# Headstage_Mainboard.net
KiCad netlist of a schematic drawn in Altium Designer
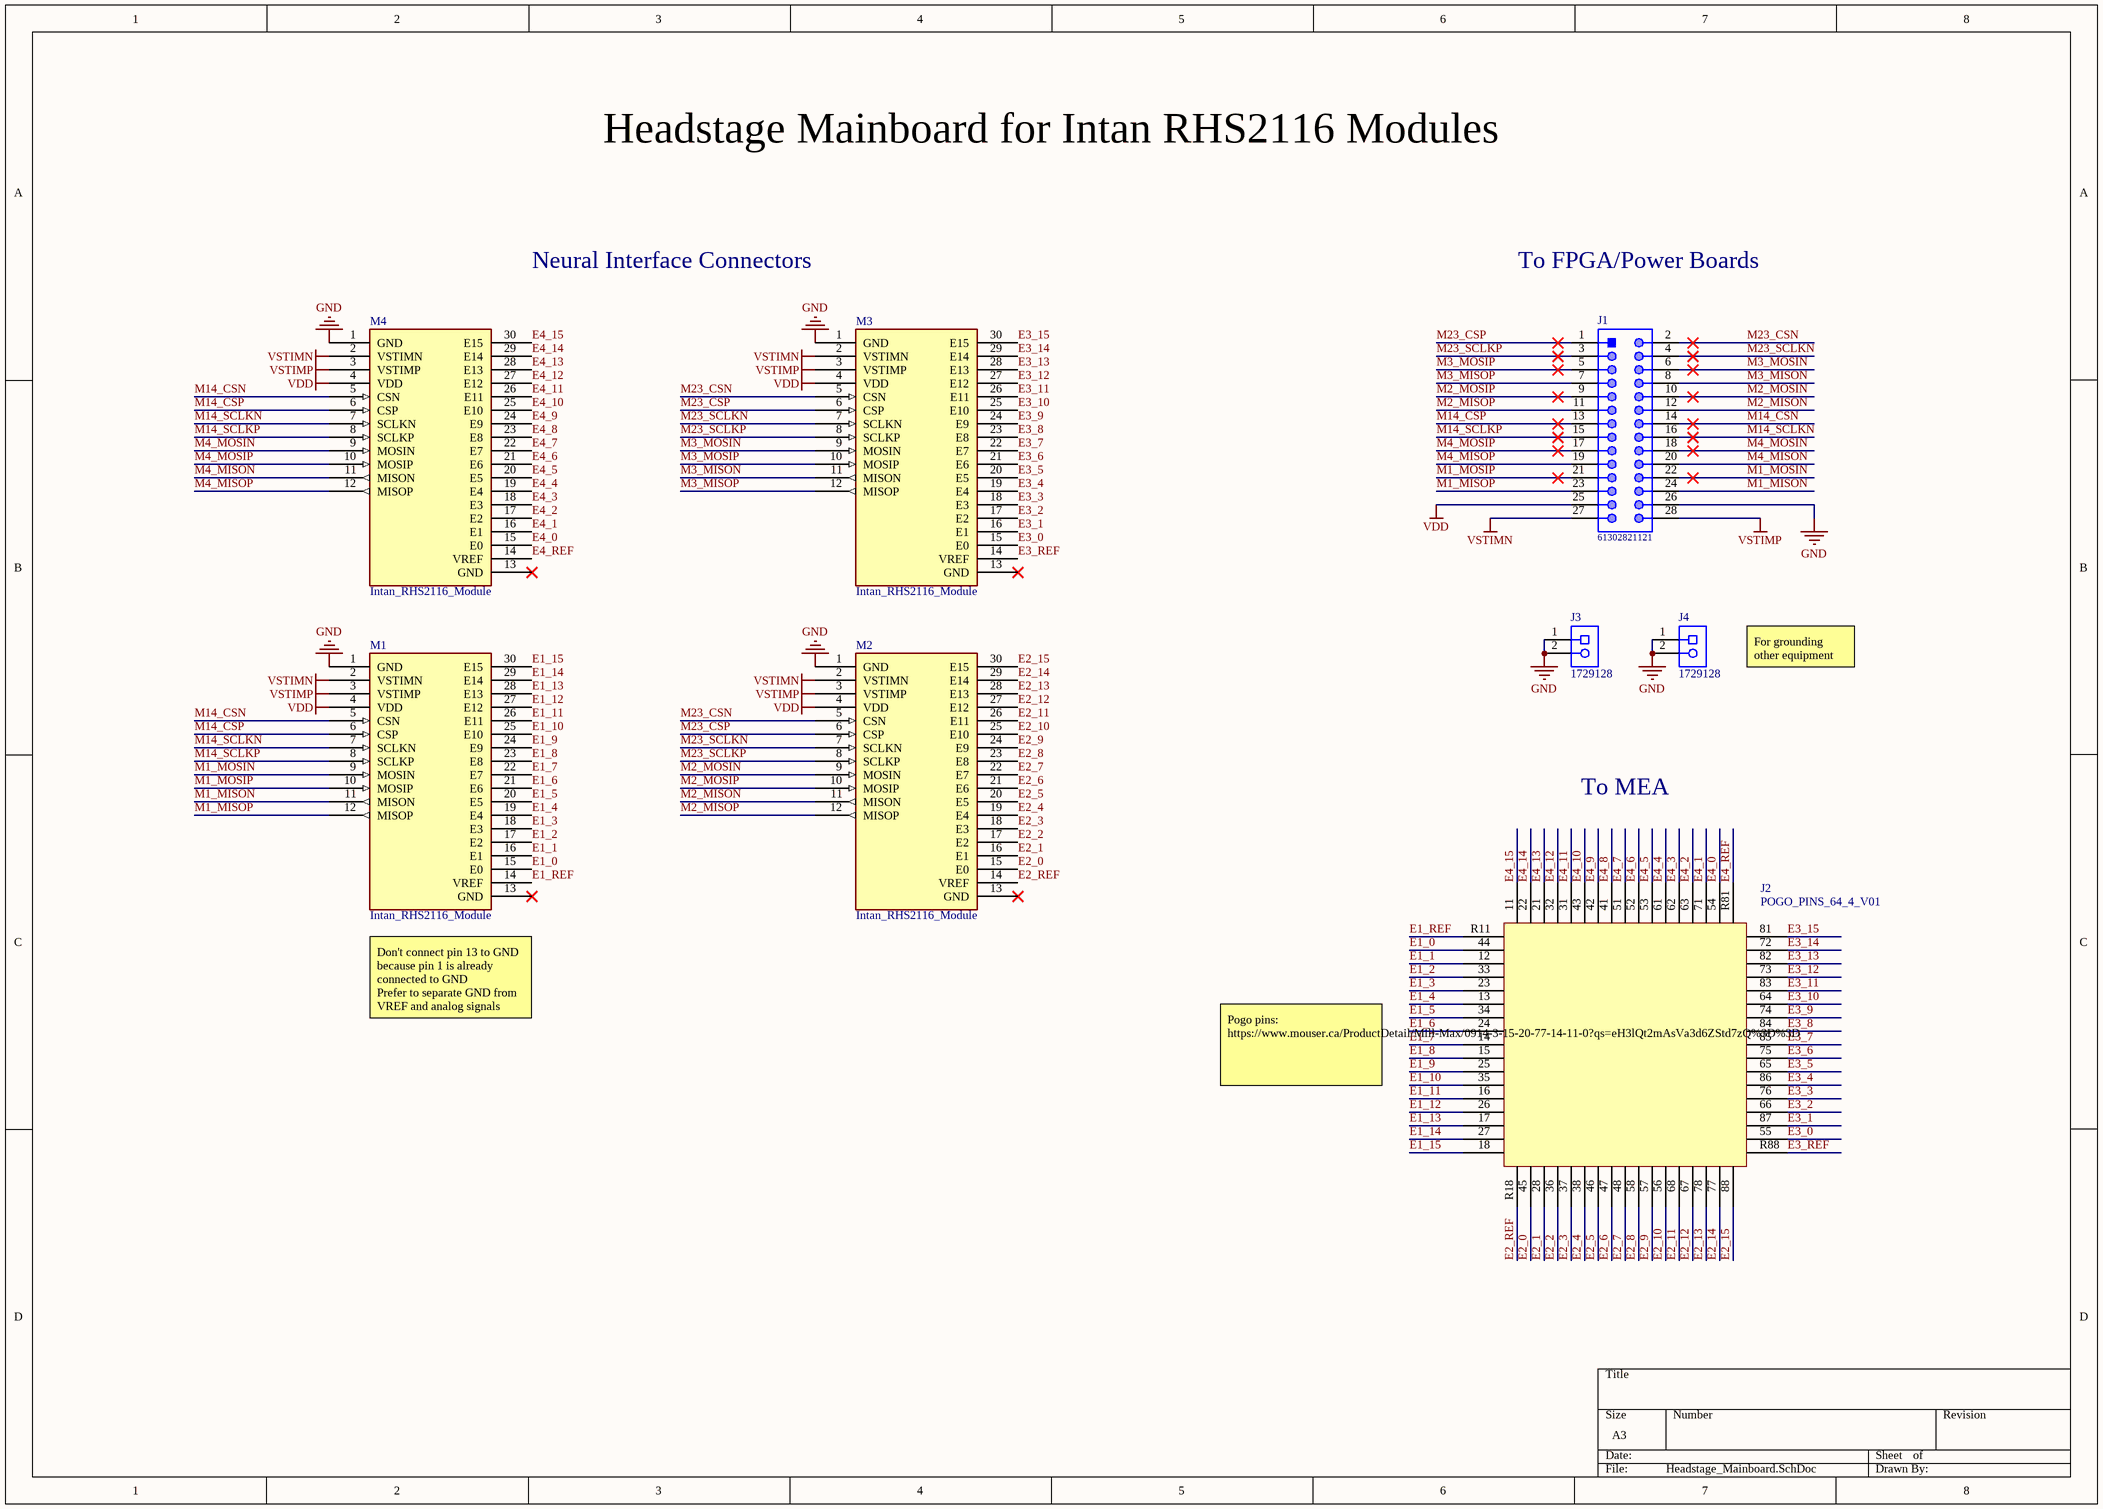
[diagram p0: Headstage_Mainboard.SchDoc]

(export (version "E")
  (design (tool "Eeschema 10.0.6"))
  (components
    (comp (ref "J1")
      (value "61302821121")
      (footprint "61302821121")
      (description "THT Vertical Pin Header WR-PHD, Pitch 2.54 mm, Dual Row, 28 pins")
      (fields (field (name "MANUFACTURER") "Wurth Elektronik") (field (name "PUBLISHER") "WurthElektronik"))
      (libsource (lib "Altium Content Vault") (part "WE-CN-2P-M-R28"))
    )
    (comp (ref "J2")
      (value "POGO_PINS_64_4_V01")
      (footprint "POGO_PINS_64_4_V01")
      (description "Pogo pins, 64 recording, 4 reference, v01")
      (libsource (lib "OpenMEA") (part "POGO_PINS_64_4_V01"))
    )
    (comp (ref "J3")
      (value "1729128")
      (footprint "PHOE-1729128-2_V")
      (description "PCB Terminal Block, 13.5 A, 400 V, 2-Pin THD, RoHS, Bulk")
      (fields (field (name "MANUFACTURER") "Phoenix Contact"))
      (libsource (lib "Altium Content Vault") (part "CN-2P-F-R2"))
    )
    (comp (ref "J4")
      (value "1729128")
      (footprint "PHOE-1729128-2_V")
      (description "PCB Terminal Block, 13.5 A, 400 V, 2-Pin THD, RoHS, Bulk")
      (fields (field (name "MANUFACTURER") "Phoenix Contact"))
      (libsource (lib "Altium Content Vault") (part "CN-2P-F-R2"))
    )
    (comp (ref "M1")
      (value "Intan_RHS2116_Module")
      (footprint "Intan_RHS2116_Module")
      (libsource (lib "OpenMEA") (part "Intan_RHS2116_Module"))
    )
    (comp (ref "M2")
      (value "Intan_RHS2116_Module")
      (footprint "Intan_RHS2116_Module")
      (libsource (lib "OpenMEA") (part "Intan_RHS2116_Module"))
    )
    (comp (ref "M3")
      (value "Intan_RHS2116_Module")
      (footprint "Intan_RHS2116_Module")
      (libsource (lib "OpenMEA") (part "Intan_RHS2116_Module"))
    )
    (comp (ref "M4")
      (value "Intan_RHS2116_Module")
      (footprint "Intan_RHS2116_Module")
      (libsource (lib "OpenMEA") (part "Intan_RHS2116_Module"))
    )
  )
  (nets
    (net (code "1") (name "/E1_0") (class "Default")
      (node (ref "J2") (pin "44") (pintype "passive"))
      (node (ref "M1") (pin "15") (pinfunction "E0_15") (pintype "passive"))
    )
    (net (code "2") (name "/E1_1") (class "Default")
      (node (ref "J2") (pin "12") (pintype "passive"))
      (node (ref "M1") (pin "16") (pinfunction "E1_16") (pintype "passive"))
    )
    (net (code "3") (name "/E1_2") (class "Default")
      (node (ref "J2") (pin "33") (pintype "passive"))
      (node (ref "M1") (pin "17") (pinfunction "E2_17") (pintype "passive"))
    )
    (net (code "4") (name "/E1_3") (class "Default")
      (node (ref "J2") (pin "23") (pintype "passive"))
      (node (ref "M1") (pin "18") (pinfunction "E3_18") (pintype "passive"))
    )
    (net (code "5") (name "/E1_4") (class "Default")
      (node (ref "J2") (pin "13") (pintype "passive"))
      (node (ref "M1") (pin "19") (pinfunction "E4_19") (pintype "passive"))
    )
    (net (code "6") (name "/E1_5") (class "Default")
      (node (ref "J2") (pin "34") (pintype "passive"))
      (node (ref "M1") (pin "20") (pinfunction "E5_20") (pintype "passive"))
    )
    (net (code "7") (name "/E1_6") (class "Default")
      (node (ref "J2") (pin "24") (pintype "passive"))
      (node (ref "M1") (pin "21") (pinfunction "E6_21") (pintype "passive"))
    )
    (net (code "8") (name "/E1_7") (class "Default")
      (node (ref "J2") (pin "14") (pintype "passive"))
      (node (ref "M1") (pin "22") (pinfunction "E7_22") (pintype "passive"))
    )
    (net (code "9") (name "/E1_8") (class "Default")
      (node (ref "J2") (pin "15") (pintype "passive"))
      (node (ref "M1") (pin "23") (pinfunction "E8_23") (pintype "passive"))
    )
    (net (code "10") (name "/E1_9") (class "Default")
      (node (ref "J2") (pin "25") (pintype "passive"))
      (node (ref "M1") (pin "24") (pinfunction "E9_24") (pintype "passive"))
    )
    (net (code "11") (name "/E1_10") (class "Default")
      (node (ref "J2") (pin "35") (pintype "passive"))
      (node (ref "M1") (pin "25") (pinfunction "E10_25") (pintype "passive"))
    )
    (net (code "12") (name "/E1_11") (class "Default")
      (node (ref "J2") (pin "16") (pintype "passive"))
      (node (ref "M1") (pin "26") (pinfunction "E11_26") (pintype "passive"))
    )
    (net (code "13") (name "/E1_12") (class "Default")
      (node (ref "J2") (pin "26") (pintype "passive"))
      (node (ref "M1") (pin "27") (pinfunction "E12_27") (pintype "passive"))
    )
    (net (code "14") (name "/E1_13") (class "Default")
      (node (ref "J2") (pin "17") (pintype "passive"))
      (node (ref "M1") (pin "28") (pinfunction "E13_28") (pintype "passive"))
    )
    (net (code "15") (name "/E1_14") (class "Default")
      (node (ref "J2") (pin "27") (pintype "passive"))
      (node (ref "M1") (pin "29") (pinfunction "E14_29") (pintype "passive"))
    )
    (net (code "16") (name "/E1_15") (class "Default")
      (node (ref "J2") (pin "18") (pintype "passive"))
      (node (ref "M1") (pin "30") (pinfunction "E15_30") (pintype "passive"))
    )
    (net (code "17") (name "/E1_REF") (class "Default")
      (node (ref "J2") (pin "R11") (pintype "passive"))
      (node (ref "M1") (pin "14") (pinfunction "VREF_14") (pintype "passive"))
    )
    (net (code "18") (name "/E2_0") (class "Default")
      (node (ref "J2") (pin "45") (pintype "passive"))
      (node (ref "M2") (pin "15") (pinfunction "E0_15") (pintype "passive"))
    )
    (net (code "19") (name "/E2_1") (class "Default")
      (node (ref "J2") (pin "28") (pintype "passive"))
      (node (ref "M2") (pin "16") (pinfunction "E1_16") (pintype "passive"))
    )
    (net (code "20") (name "/E2_2") (class "Default")
      (node (ref "J2") (pin "36") (pintype "passive"))
      (node (ref "M2") (pin "17") (pinfunction "E2_17") (pintype "passive"))
    )
    (net (code "21") (name "/E2_3") (class "Default")
      (node (ref "J2") (pin "37") (pintype "passive"))
      (node (ref "M2") (pin "18") (pinfunction "E3_18") (pintype "passive"))
    )
    (net (code "22") (name "/E2_4") (class "Default")
      (node (ref "J2") (pin "38") (pintype "passive"))
      (node (ref "M2") (pin "19") (pinfunction "E4_19") (pintype "passive"))
    )
    (net (code "23") (name "/E2_5") (class "Default")
      (node (ref "J2") (pin "46") (pintype "passive"))
      (node (ref "M2") (pin "20") (pinfunction "E5_20") (pintype "passive"))
    )
    (net (code "24") (name "/E2_6") (class "Default")
      (node (ref "J2") (pin "47") (pintype "passive"))
      (node (ref "M2") (pin "21") (pinfunction "E6_21") (pintype "passive"))
    )
    (net (code "25") (name "/E2_7") (class "Default")
      (node (ref "J2") (pin "48") (pintype "passive"))
      (node (ref "M2") (pin "22") (pinfunction "E7_22") (pintype "passive"))
    )
    (net (code "26") (name "/E2_8") (class "Default")
      (node (ref "J2") (pin "58") (pintype "passive"))
      (node (ref "M2") (pin "23") (pinfunction "E8_23") (pintype "passive"))
    )
    (net (code "27") (name "/E2_9") (class "Default")
      (node (ref "J2") (pin "57") (pintype "passive"))
      (node (ref "M2") (pin "24") (pinfunction "E9_24") (pintype "passive"))
    )
    (net (code "28") (name "/E2_10") (class "Default")
      (node (ref "J2") (pin "56") (pintype "passive"))
      (node (ref "M2") (pin "25") (pinfunction "E10_25") (pintype "passive"))
    )
    (net (code "29") (name "/E2_11") (class "Default")
      (node (ref "J2") (pin "68") (pintype "passive"))
      (node (ref "M2") (pin "26") (pinfunction "E11_26") (pintype "passive"))
    )
    (net (code "30") (name "/E2_12") (class "Default")
      (node (ref "J2") (pin "67") (pintype "passive"))
      (node (ref "M2") (pin "27") (pinfunction "E12_27") (pintype "passive"))
    )
    (net (code "31") (name "/E2_13") (class "Default")
      (node (ref "J2") (pin "78") (pintype "passive"))
      (node (ref "M2") (pin "28") (pinfunction "E13_28") (pintype "passive"))
    )
    (net (code "32") (name "/E2_14") (class "Default")
      (node (ref "J2") (pin "77") (pintype "passive"))
      (node (ref "M2") (pin "29") (pinfunction "E14_29") (pintype "passive"))
    )
    (net (code "33") (name "/E2_15") (class "Default")
      (node (ref "J2") (pin "88") (pintype "passive"))
      (node (ref "M2") (pin "30") (pinfunction "E15_30") (pintype "passive"))
    )
    (net (code "34") (name "/E2_REF") (class "Default")
      (node (ref "J2") (pin "R18") (pintype "passive"))
      (node (ref "M2") (pin "14") (pinfunction "VREF_14") (pintype "passive"))
    )
    (net (code "35") (name "/E3_0") (class "Default")
      (node (ref "J2") (pin "55") (pintype "passive"))
      (node (ref "M3") (pin "15") (pinfunction "E0_15") (pintype "passive"))
    )
    (net (code "36") (name "/E3_1") (class "Default")
      (node (ref "J2") (pin "87") (pintype "passive"))
      (node (ref "M3") (pin "16") (pinfunction "E1_16") (pintype "passive"))
    )
    (net (code "37") (name "/E3_2") (class "Default")
      (node (ref "J2") (pin "66") (pintype "passive"))
      (node (ref "M3") (pin "17") (pinfunction "E2_17") (pintype "passive"))
    )
    (net (code "38") (name "/E3_3") (class "Default")
      (node (ref "J2") (pin "76") (pintype "passive"))
      (node (ref "M3") (pin "18") (pinfunction "E3_18") (pintype "passive"))
    )
    (net (code "39") (name "/E3_4") (class "Default")
      (node (ref "J2") (pin "86") (pintype "passive"))
      (node (ref "M3") (pin "19") (pinfunction "E4_19") (pintype "passive"))
    )
    (net (code "40") (name "/E3_5") (class "Default")
      (node (ref "J2") (pin "65") (pintype "passive"))
      (node (ref "M3") (pin "20") (pinfunction "E5_20") (pintype "passive"))
    )
    (net (code "41") (name "/E3_6") (class "Default")
      (node (ref "J2") (pin "75") (pintype "passive"))
      (node (ref "M3") (pin "21") (pinfunction "E6_21") (pintype "passive"))
    )
    (net (code "42") (name "/E3_7") (class "Default")
      (node (ref "J2") (pin "85") (pintype "passive"))
      (node (ref "M3") (pin "22") (pinfunction "E7_22") (pintype "passive"))
    )
    (net (code "43") (name "/E3_8") (class "Default")
      (node (ref "J2") (pin "84") (pintype "passive"))
      (node (ref "M3") (pin "23") (pinfunction "E8_23") (pintype "passive"))
    )
    (net (code "44") (name "/E3_9") (class "Default")
      (node (ref "J2") (pin "74") (pintype "passive"))
      (node (ref "M3") (pin "24") (pinfunction "E9_24") (pintype "passive"))
    )
    (net (code "45") (name "/E3_10") (class "Default")
      (node (ref "J2") (pin "64") (pintype "passive"))
      (node (ref "M3") (pin "25") (pinfunction "E10_25") (pintype "passive"))
    )
    (net (code "46") (name "/E3_11") (class "Default")
      (node (ref "J2") (pin "83") (pintype "passive"))
      (node (ref "M3") (pin "26") (pinfunction "E11_26") (pintype "passive"))
    )
    (net (code "47") (name "/E3_12") (class "Default")
      (node (ref "J2") (pin "73") (pintype "passive"))
      (node (ref "M3") (pin "27") (pinfunction "E12_27") (pintype "passive"))
    )
    (net (code "48") (name "/E3_13") (class "Default")
      (node (ref "J2") (pin "82") (pintype "passive"))
      (node (ref "M3") (pin "28") (pinfunction "E13_28") (pintype "passive"))
    )
    (net (code "49") (name "/E3_14") (class "Default")
      (node (ref "J2") (pin "72") (pintype "passive"))
      (node (ref "M3") (pin "29") (pinfunction "E14_29") (pintype "passive"))
    )
    (net (code "50") (name "/E3_15") (class "Default")
      (node (ref "J2") (pin "81") (pintype "passive"))
      (node (ref "M3") (pin "30") (pinfunction "E15_30") (pintype "passive"))
    )
    (net (code "51") (name "/E3_REF") (class "Default")
      (node (ref "J2") (pin "R88") (pintype "passive"))
      (node (ref "M3") (pin "14") (pinfunction "VREF_14") (pintype "passive"))
    )
    (net (code "52") (name "/E4_0") (class "Default")
      (node (ref "J2") (pin "54") (pintype "passive"))
      (node (ref "M4") (pin "15") (pinfunction "E0_15") (pintype "passive"))
    )
    (net (code "53") (name "/E4_1") (class "Default")
      (node (ref "J2") (pin "71") (pintype "passive"))
      (node (ref "M4") (pin "16") (pinfunction "E1_16") (pintype "passive"))
    )
    (net (code "54") (name "/E4_2") (class "Default")
      (node (ref "J2") (pin "63") (pintype "passive"))
      (node (ref "M4") (pin "17") (pinfunction "E2_17") (pintype "passive"))
    )
    (net (code "55") (name "/E4_3") (class "Default")
      (node (ref "J2") (pin "62") (pintype "passive"))
      (node (ref "M4") (pin "18") (pinfunction "E3_18") (pintype "passive"))
    )
    (net (code "56") (name "/E4_4") (class "Default")
      (node (ref "J2") (pin "61") (pintype "passive"))
      (node (ref "M4") (pin "19") (pinfunction "E4_19") (pintype "passive"))
    )
    (net (code "57") (name "/E4_5") (class "Default")
      (node (ref "J2") (pin "53") (pintype "passive"))
      (node (ref "M4") (pin "20") (pinfunction "E5_20") (pintype "passive"))
    )
    (net (code "58") (name "/E4_6") (class "Default")
      (node (ref "J2") (pin "52") (pintype "passive"))
      (node (ref "M4") (pin "21") (pinfunction "E6_21") (pintype "passive"))
    )
    (net (code "59") (name "/E4_7") (class "Default")
      (node (ref "J2") (pin "51") (pintype "passive"))
      (node (ref "M4") (pin "22") (pinfunction "E7_22") (pintype "passive"))
    )
    (net (code "60") (name "/E4_8") (class "Default")
      (node (ref "J2") (pin "41") (pintype "passive"))
      (node (ref "M4") (pin "23") (pinfunction "E8_23") (pintype "passive"))
    )
    (net (code "61") (name "/E4_9") (class "Default")
      (node (ref "J2") (pin "42") (pintype "passive"))
      (node (ref "M4") (pin "24") (pinfunction "E9_24") (pintype "passive"))
    )
    (net (code "62") (name "/E4_10") (class "Default")
      (node (ref "J2") (pin "43") (pintype "passive"))
      (node (ref "M4") (pin "25") (pinfunction "E10_25") (pintype "passive"))
    )
    (net (code "63") (name "/E4_11") (class "Default")
      (node (ref "J2") (pin "31") (pintype "passive"))
      (node (ref "M4") (pin "26") (pinfunction "E11_26") (pintype "passive"))
    )
    (net (code "64") (name "/E4_12") (class "Default")
      (node (ref "J2") (pin "32") (pintype "passive"))
      (node (ref "M4") (pin "27") (pinfunction "E12_27") (pintype "passive"))
    )
    (net (code "65") (name "/E4_13") (class "Default")
      (node (ref "J2") (pin "21") (pintype "passive"))
      (node (ref "M4") (pin "28") (pinfunction "E13_28") (pintype "passive"))
    )
    (net (code "66") (name "/E4_14") (class "Default")
      (node (ref "J2") (pin "22") (pintype "passive"))
      (node (ref "M4") (pin "29") (pinfunction "E14_29") (pintype "passive"))
    )
    (net (code "67") (name "/E4_15") (class "Default")
      (node (ref "J2") (pin "11") (pintype "passive"))
      (node (ref "M4") (pin "30") (pinfunction "E15_30") (pintype "passive"))
    )
    (net (code "68") (name "/E4_REF") (class "Default")
      (node (ref "J2") (pin "R81") (pintype "passive"))
      (node (ref "M4") (pin "14") (pinfunction "VREF_14") (pintype "passive"))
    )
    (net (code "69") (name "/M1_MISON") (class "Default")
      (node (ref "J1") (pin "24") (pinfunction "24_24") (pintype "passive"))
      (node (ref "M1") (pin "11") (pinfunction "MISON_11") (pintype "output"))
    )
    (net (code "70") (name "/M1_MISOP") (class "Default")
      (node (ref "J1") (pin "23") (pinfunction "23_23") (pintype "passive"))
      (node (ref "M1") (pin "12") (pinfunction "MISOP_12") (pintype "output"))
    )
    (net (code "71") (name "/M1_MOSIN") (class "Default")
      (node (ref "J1") (pin "22") (pinfunction "22_22") (pintype "passive"))
      (node (ref "M1") (pin "9") (pinfunction "MOSIN_9") (pintype "input"))
    )
    (net (code "72") (name "/M1_MOSIP") (class "Default")
      (node (ref "J1") (pin "21") (pinfunction "21_21") (pintype "passive"))
      (node (ref "M1") (pin "10") (pinfunction "MOSIP_10") (pintype "input"))
    )
    (net (code "73") (name "/M2_MISON") (class "Default")
      (node (ref "J1") (pin "12") (pinfunction "12_12") (pintype "passive"))
      (node (ref "M2") (pin "11") (pinfunction "MISON_11") (pintype "output"))
    )
    (net (code "74") (name "/M2_MISOP") (class "Default")
      (node (ref "J1") (pin "11") (pinfunction "11_11") (pintype "passive"))
      (node (ref "M2") (pin "12") (pinfunction "MISOP_12") (pintype "output"))
    )
    (net (code "75") (name "/M2_MOSIN") (class "Default")
      (node (ref "J1") (pin "10") (pinfunction "10_10") (pintype "passive"))
      (node (ref "M2") (pin "9") (pinfunction "MOSIN_9") (pintype "input"))
    )
    (net (code "76") (name "/M2_MOSIP") (class "Default")
      (node (ref "J1") (pin "9") (pinfunction "9_9") (pintype "passive"))
      (node (ref "M2") (pin "10") (pinfunction "MOSIP_10") (pintype "input"))
    )
    (net (code "77") (name "/M3_MISON") (class "Default")
      (node (ref "J1") (pin "8") (pinfunction "8_8") (pintype "passive"))
      (node (ref "M3") (pin "11") (pinfunction "MISON_11") (pintype "output"))
    )
    (net (code "78") (name "/M3_MISOP") (class "Default")
      (node (ref "J1") (pin "7") (pinfunction "7_7") (pintype "passive"))
      (node (ref "M3") (pin "12") (pinfunction "MISOP_12") (pintype "output"))
    )
    (net (code "79") (name "/M3_MOSIN") (class "Default")
      (node (ref "J1") (pin "6") (pinfunction "6_6") (pintype "passive"))
      (node (ref "M3") (pin "9") (pinfunction "MOSIN_9") (pintype "input"))
    )
    (net (code "80") (name "/M3_MOSIP") (class "Default")
      (node (ref "J1") (pin "5") (pinfunction "5_5") (pintype "passive"))
      (node (ref "M3") (pin "10") (pinfunction "MOSIP_10") (pintype "input"))
    )
    (net (code "81") (name "/M4_MISON") (class "Default")
      (node (ref "J1") (pin "20") (pinfunction "20_20") (pintype "passive"))
      (node (ref "M4") (pin "11") (pinfunction "MISON_11") (pintype "output"))
    )
    (net (code "82") (name "/M4_MISOP") (class "Default")
      (node (ref "J1") (pin "19") (pinfunction "19_19") (pintype "passive"))
      (node (ref "M4") (pin "12") (pinfunction "MISOP_12") (pintype "output"))
    )
    (net (code "83") (name "/M4_MOSIN") (class "Default")
      (node (ref "J1") (pin "18") (pinfunction "18_18") (pintype "passive"))
      (node (ref "M4") (pin "9") (pinfunction "MOSIN_9") (pintype "input"))
    )
    (net (code "84") (name "/M4_MOSIP") (class "Default")
      (node (ref "J1") (pin "17") (pinfunction "17_17") (pintype "passive"))
      (node (ref "M4") (pin "10") (pinfunction "MOSIP_10") (pintype "input"))
    )
    (net (code "85") (name "/M14_CSN") (class "Default")
      (node (ref "J1") (pin "14") (pinfunction "14_14") (pintype "passive"))
      (node (ref "M1") (pin "5") (pinfunction "CSN_5") (pintype "input"))
      (node (ref "M4") (pin "5") (pinfunction "CSN_5") (pintype "input"))
    )
    (net (code "86") (name "/M14_CSP") (class "Default")
      (node (ref "J1") (pin "13") (pinfunction "13_13") (pintype "passive"))
      (node (ref "M1") (pin "6") (pinfunction "CSP_6") (pintype "input"))
      (node (ref "M4") (pin "6") (pinfunction "CSP_6") (pintype "input"))
    )
    (net (code "87") (name "/M14_SCLKN") (class "Default")
      (node (ref "J1") (pin "16") (pinfunction "16_16") (pintype "passive"))
      (node (ref "M1") (pin "7") (pinfunction "SCLKN_7") (pintype "input"))
      (node (ref "M4") (pin "7") (pinfunction "SCLKN_7") (pintype "input"))
    )
    (net (code "88") (name "/M14_SCLKP") (class "Default")
      (node (ref "J1") (pin "15") (pinfunction "15_15") (pintype "passive"))
      (node (ref "M1") (pin "8") (pinfunction "SCLKP_8") (pintype "input"))
      (node (ref "M4") (pin "8") (pinfunction "SCLKP_8") (pintype "input"))
    )
    (net (code "89") (name "/M23_CSN") (class "Default")
      (node (ref "J1") (pin "2") (pinfunction "2_2") (pintype "passive"))
      (node (ref "M2") (pin "5") (pinfunction "CSN_5") (pintype "input"))
      (node (ref "M3") (pin "5") (pinfunction "CSN_5") (pintype "input"))
    )
    (net (code "90") (name "/M23_CSP") (class "Default")
      (node (ref "J1") (pin "1") (pinfunction "1_1") (pintype "passive"))
      (node (ref "M2") (pin "6") (pinfunction "CSP_6") (pintype "input"))
      (node (ref "M3") (pin "6") (pinfunction "CSP_6") (pintype "input"))
    )
    (net (code "91") (name "/M23_SCLKN") (class "Default")
      (node (ref "J1") (pin "4") (pinfunction "4_4") (pintype "passive"))
      (node (ref "M2") (pin "7") (pinfunction "SCLKN_7") (pintype "input"))
      (node (ref "M3") (pin "7") (pinfunction "SCLKN_7") (pintype "input"))
    )
    (net (code "92") (name "/M23_SCLKP") (class "Default")
      (node (ref "J1") (pin "3") (pinfunction "3_3") (pintype "passive"))
      (node (ref "M2") (pin "8") (pinfunction "SCLKP_8") (pintype "input"))
      (node (ref "M3") (pin "8") (pinfunction "SCLKP_8") (pintype "input"))
    )
    (net (code "93") (name "GND") (class "Default")
      (node (ref "J1") (pin "26") (pinfunction "26_26") (pintype "passive"))
      (node (ref "J3") (pin "1") (pinfunction "1_1") (pintype "passive"))
      (node (ref "J3") (pin "2") (pinfunction "2_2") (pintype "passive"))
      (node (ref "J4") (pin "1") (pinfunction "1_1") (pintype "passive"))
      (node (ref "J4") (pin "2") (pinfunction "2_2") (pintype "passive"))
      (node (ref "M1") (pin "1") (pinfunction "GND_1") (pintype "power_in"))
      (node (ref "M2") (pin "1") (pinfunction "GND_1") (pintype "power_in"))
      (node (ref "M3") (pin "1") (pinfunction "GND_1") (pintype "power_in"))
      (node (ref "M4") (pin "1") (pinfunction "GND_1") (pintype "power_in"))
    )
    (net (code "94") (name "VDD") (class "Default")
      (node (ref "J1") (pin "25") (pinfunction "25_25") (pintype "passive"))
      (node (ref "M1") (pin "4") (pinfunction "VDD_4") (pintype "power_in"))
      (node (ref "M2") (pin "4") (pinfunction "VDD_4") (pintype "power_in"))
      (node (ref "M3") (pin "4") (pinfunction "VDD_4") (pintype "power_in"))
      (node (ref "M4") (pin "4") (pinfunction "VDD_4") (pintype "power_in"))
    )
    (net (code "95") (name "VSTIMN") (class "Default")
      (node (ref "J1") (pin "27") (pinfunction "27_27") (pintype "passive"))
      (node (ref "M1") (pin "2") (pinfunction "VSTIMN_2") (pintype "power_in"))
      (node (ref "M2") (pin "2") (pinfunction "VSTIMN_2") (pintype "power_in"))
      (node (ref "M3") (pin "2") (pinfunction "VSTIMN_2") (pintype "power_in"))
      (node (ref "M4") (pin "2") (pinfunction "VSTIMN_2") (pintype "power_in"))
    )
    (net (code "96") (name "VSTIMP") (class "Default")
      (node (ref "J1") (pin "28") (pinfunction "28_28") (pintype "passive"))
      (node (ref "M1") (pin "3") (pinfunction "VSTIMP_3") (pintype "power_in"))
      (node (ref "M2") (pin "3") (pinfunction "VSTIMP_3") (pintype "power_in"))
      (node (ref "M3") (pin "3") (pinfunction "VSTIMP_3") (pintype "power_in"))
      (node (ref "M4") (pin "3") (pinfunction "VSTIMP_3") (pintype "power_in"))
    )
    (net (code "97") (name "unconnected-(M1-GND-Pad13)") (class "Default")
      (node (ref "M1") (pin "13") (pinfunction "GND_13") (pintype "power_in+no_connect"))
    )
    (net (code "98") (name "unconnected-(M2-GND-Pad13)") (class "Default")
      (node (ref "M2") (pin "13") (pinfunction "GND_13") (pintype "power_in+no_connect"))
    )
    (net (code "99") (name "unconnected-(M3-GND-Pad13)") (class "Default")
      (node (ref "M3") (pin "13") (pinfunction "GND_13") (pintype "power_in+no_connect"))
    )
    (net (code "100") (name "unconnected-(M4-GND-Pad13)") (class "Default")
      (node (ref "M4") (pin "13") (pinfunction "GND_13") (pintype "power_in+no_connect"))
    )
  )
)
